# thermistorADC.net
KiCad netlist of a schematic drawn in Altium Designer
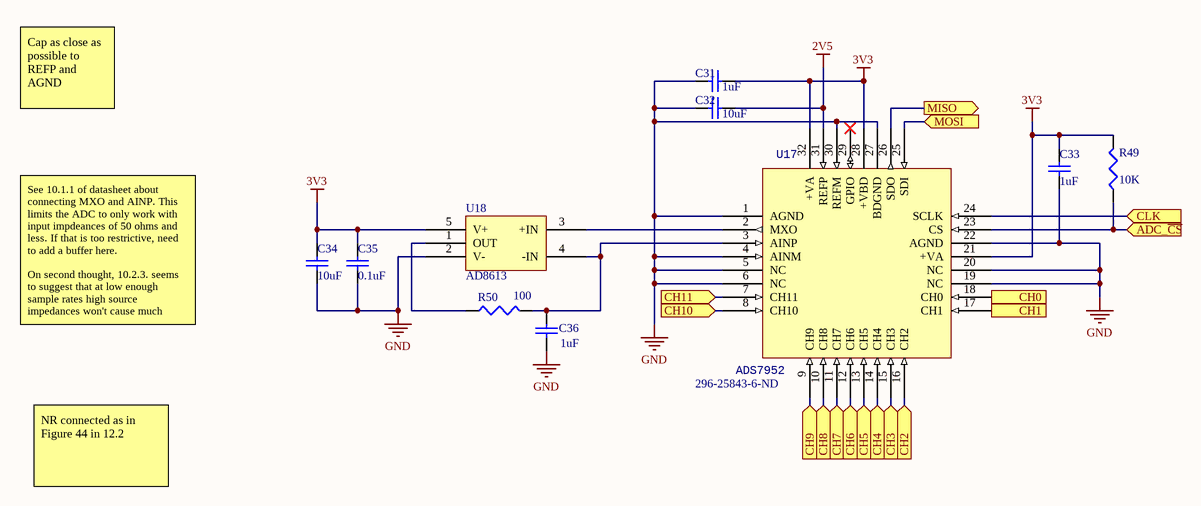
[diagram p0: thermistorADC.SchDoc]

(export (version "E")
  (design (tool "Eeschema 10.0.6"))
  (components
    (comp (ref "C31")
      (value "1uF")
      (footprint "1608[0603]")
      (description "Capacitor (Semiconductor SIM Model)")
      (fields (field (name "PUBLISHER") "Altium Limited"))
      (libsource (lib "Miscellaneous Devices") (part "Cap Semi"))
    )
    (comp (ref "C32")
      (value "10uF")
      (footprint "1608[0603]")
      (description "Capacitor")
      (fields (field (name "PUBLISHER") "Altium Limited"))
      (libsource (lib "Miscellaneous Devices") (part "Cap"))
    )
    (comp (ref "C33")
      (value "1uF")
      (footprint "1608[0603]")
      (description "Capacitor (Semiconductor SIM Model)")
      (fields (field (name "PUBLISHER") "Altium Limited"))
      (libsource (lib "Miscellaneous Devices") (part "Cap Semi"))
    )
    (comp (ref "C34")
      (value "10uF")
      (footprint "1608[0603]")
      (description "Capacitor (Semiconductor SIM Model)")
      (fields (field (name "PUBLISHER") "Altium Limited"))
      (libsource (lib "Miscellaneous Devices") (part "Cap Semi"))
    )
    (comp (ref "C35")
      (value "0.1uF")
      (footprint "1608[0603]")
      (description "Capacitor (Semiconductor SIM Model)")
      (fields (field (name "PUBLISHER") "Altium Limited"))
      (libsource (lib "Miscellaneous Devices") (part "Cap Semi"))
    )
    (comp (ref "C36")
      (value "1uF")
      (footprint "1608[0603]")
      (description "Capacitor (Semiconductor SIM Model)")
      (fields (field (name "PUBLISHER") "Altium Limited"))
      (libsource (lib "Miscellaneous Devices") (part "Cap Semi"))
    )
    (comp (ref "R49")
      (value "10K")
      (footprint "J1-0603")
      (description "Resistor")
      (fields (field (name "PUBLISHER") "Altium Limited"))
      (libsource (lib "Miscellaneous Devices") (part "Res3"))
    )
    (comp (ref "R50")
      (value "100")
      (footprint "J1-0603")
      (description "Resistor")
      (fields (field (name "PUBLISHER") "Altium Limited"))
      (libsource (lib "Miscellaneous Devices") (part "Res3"))
    )
    (comp (ref "U17")
      (value "ADS7952")
      (footprint "QFN50P500X500X100-32N")
      (description "ADC")
      (fields (field (name "SUPPLIER PART NUMBER 1") "296-25843-6-ND"))
      (libsource (lib "heron-general") (part "ADS7952"))
    )
    (comp (ref "U18")
      (value "AD8613")
      (footprint "SOP-65P200X125-5N")
      (description "Low power, low noise rail-to-rail op-amp.")
      (libsource (lib "PAY") (part "AD8613"))
    )
  )
  (nets
    (net (code "1") (name "/ADC_~{CS}") (class "Default")
      (node (ref "R49") (pin "1") (pinfunction "1_1") (pintype "passive"))
      (node (ref "U17") (pin "23") (pinfunction "CS_23") (pintype "input"))
    )
    (net (code "2") (name "/CH0") (class "Default")
      (node (ref "U17") (pin "18") (pinfunction "CH0_18") (pintype "input"))
    )
    (net (code "3") (name "/CH1") (class "Default")
      (node (ref "U17") (pin "17") (pinfunction "CH1_17") (pintype "input"))
    )
    (net (code "4") (name "/CH2") (class "Default")
      (node (ref "U17") (pin "16") (pinfunction "CH2_16") (pintype "input"))
    )
    (net (code "5") (name "/CH3") (class "Default")
      (node (ref "U17") (pin "15") (pinfunction "CH3_15") (pintype "input"))
    )
    (net (code "6") (name "/CH4") (class "Default")
      (node (ref "U17") (pin "14") (pinfunction "CH4_14") (pintype "input"))
    )
    (net (code "7") (name "/CH5") (class "Default")
      (node (ref "U17") (pin "13") (pinfunction "CH5_13") (pintype "input"))
    )
    (net (code "8") (name "/CH6") (class "Default")
      (node (ref "U17") (pin "12") (pinfunction "CH6_12") (pintype "input"))
    )
    (net (code "9") (name "/CH7") (class "Default")
      (node (ref "U17") (pin "11") (pinfunction "CH7_11") (pintype "input"))
    )
    (net (code "10") (name "/CH8") (class "Default")
      (node (ref "U17") (pin "10") (pinfunction "CH8_10") (pintype "input"))
    )
    (net (code "11") (name "/CH9") (class "Default")
      (node (ref "U17") (pin "9") (pinfunction "CH9_9") (pintype "input"))
    )
    (net (code "12") (name "/CH10") (class "Default")
      (node (ref "U17") (pin "8") (pinfunction "CH10_8") (pintype "input"))
    )
    (net (code "13") (name "/CH11") (class "Default")
      (node (ref "U17") (pin "7") (pinfunction "CH11_7") (pintype "input"))
    )
    (net (code "14") (name "/CLK") (class "Default")
      (node (ref "U17") (pin "24") (pinfunction "SCLK_24") (pintype "input"))
    )
    (net (code "15") (name "/MISO") (class "Default")
      (node (ref "U17") (pin "26") (pinfunction "SDO_26") (pintype "output"))
    )
    (net (code "16") (name "/MOSI") (class "Default")
      (node (ref "U17") (pin "25") (pinfunction "SDI_25") (pintype "input"))
    )
    (net (code "17") (name "2V5") (class "Default")
      (node (ref "C32") (pin "2") (pinfunction "2_2") (pintype "passive"))
      (node (ref "U17") (pin "31") (pinfunction "REFP_31") (pintype "input"))
    )
    (net (code "18") (name "3V3") (class "Default")
      (node (ref "C31") (pin "2") (pinfunction "2_2") (pintype "passive"))
      (node (ref "C33") (pin "2") (pinfunction "2_2") (pintype "passive"))
      (node (ref "C34") (pin "2") (pinfunction "2_2") (pintype "passive"))
      (node (ref "C35") (pin "2") (pinfunction "2_2") (pintype "passive"))
      (node (ref "R49") (pin "2") (pinfunction "2_2") (pintype "passive"))
      (node (ref "U17") (pin "21") (pinfunction "+VA_21") (pintype "power_in"))
      (node (ref "U17") (pin "28") (pinfunction "+VBD_28") (pintype "power_in"))
      (node (ref "U17") (pin "32") (pinfunction "+VA_32") (pintype "power_in"))
      (node (ref "U18") (pin "5") (pinfunction "V+_5") (pintype "passive"))
    )
    (net (code "19") (name "GND") (class "Default")
      (node (ref "C31") (pin "1") (pinfunction "1_1") (pintype "passive"))
      (node (ref "C32") (pin "1") (pinfunction "1_1") (pintype "passive"))
      (node (ref "C33") (pin "1") (pinfunction "1_1") (pintype "passive"))
      (node (ref "C34") (pin "1") (pinfunction "1_1") (pintype "passive"))
      (node (ref "C35") (pin "1") (pinfunction "1_1") (pintype "passive"))
      (node (ref "C36") (pin "1") (pinfunction "1_1") (pintype "passive"))
      (node (ref "U17") (pin "1") (pinfunction "AGND_1") (pintype "power_in"))
      (node (ref "U17") (pin "19") (pinfunction "NC_19") (pintype "passive"))
      (node (ref "U17") (pin "20") (pinfunction "NC_20") (pintype "passive"))
      (node (ref "U17") (pin "22") (pinfunction "AGND_22") (pintype "power_in"))
      (node (ref "U17") (pin "27") (pinfunction "BDGND_27") (pintype "power_in"))
      (node (ref "U17") (pin "30") (pinfunction "REFM_30") (pintype "input"))
      (node (ref "U17") (pin "4") (pinfunction "AINM_4") (pintype "input"))
      (node (ref "U17") (pin "5") (pinfunction "NC_5") (pintype "passive"))
      (node (ref "U17") (pin "6") (pinfunction "NC_6") (pintype "passive"))
      (node (ref "U18") (pin "2") (pinfunction "V-_2") (pintype "passive"))
    )
    (net (code "20") (name "Net-(U17-AINP)") (class "Default")
      (node (ref "C36") (pin "2") (pinfunction "2_2") (pintype "passive"))
      (node (ref "R50") (pin "2") (pinfunction "2_2") (pintype "passive"))
      (node (ref "U17") (pin "3") (pinfunction "AINP_3") (pintype "input"))
      (node (ref "U18") (pin "4") (pinfunction "-IN_4") (pintype "passive"))
    )
    (net (code "21") (name "Net-(U17-MXO)") (class "Default")
      (node (ref "U17") (pin "2") (pinfunction "MXO_2") (pintype "output"))
      (node (ref "U18") (pin "3") (pinfunction "+IN_3") (pintype "passive"))
    )
    (net (code "22") (name "Net-(U18-OUT)") (class "Default")
      (node (ref "R50") (pin "1") (pinfunction "1_1") (pintype "passive"))
      (node (ref "U18") (pin "1") (pinfunction "OUT_1") (pintype "passive"))
    )
    (net (code "23") (name "unconnected-(U17-GPIO-Pad29)") (class "Default")
      (node (ref "U17") (pin "29") (pinfunction "GPIO_29") (pintype "bidirectional+no_connect"))
    )
  )
)
